# Microcontroller.net
KiCad netlist of a schematic drawn in Altium Designer
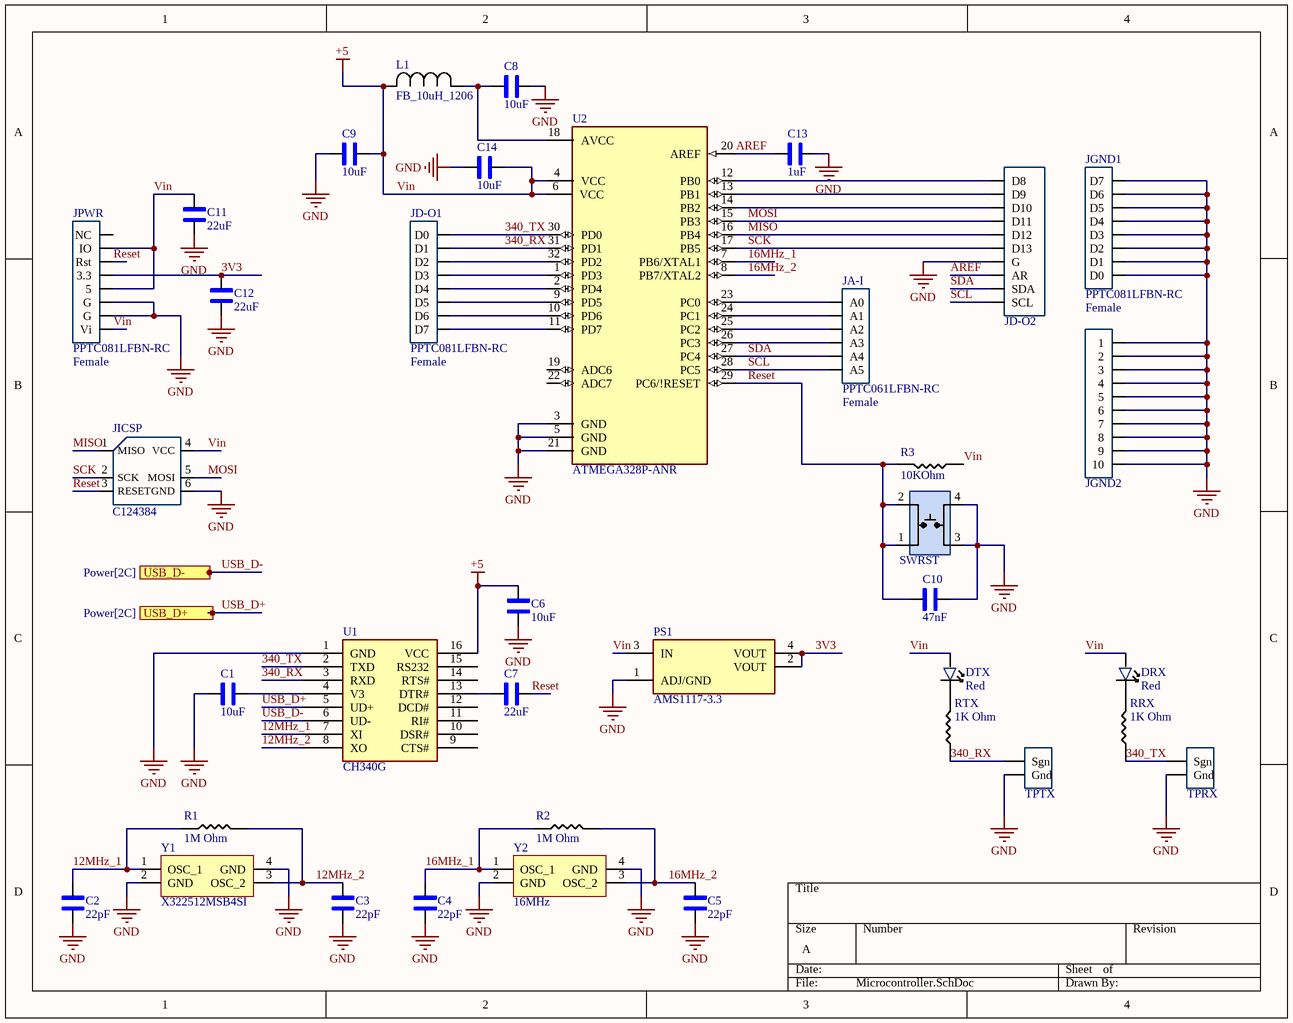
[diagram p0: Microcontroller.SchDoc]

(export (version "E")
  (design (tool "Eeschema 10.0.6"))
  (components
    (comp (ref "C1")
      (value "10uF")
      (footprint "1206_Passive_Capacitor")
      (description "10uF ±10% 50V X5R 1206 Multilayer Ceramic Capacitors MLCC - SMD/SMT RoHS")
      (fields (field (name "LCSC PART#") "C13585") (field (name "MFR PART #") "CL31A106KBHNNNE"))
      (libsource (lib "ECEN5730Lib") (part "C_10uF_1206"))
    )
    (comp (ref "C2")
      (value "22pF")
      (footprint "1206_Passive_Capacitor")
      (description "22pF ±5% 1kV C0G 1206 Multilayer Ceramic Capacitors MLCC - SMD/SMT RoHS")
      (fields (field (name "LCSC PART#") "C107174") (field (name "MFR PART #") "CC1206JKNPOCBN220"))
      (libsource (lib "ECEN5730Lib") (part "C_22pF_1206"))
    )
    (comp (ref "C3")
      (value "22pF")
      (footprint "1206_Passive_Capacitor")
      (description "22pF ±5% 1kV C0G 1206 Multilayer Ceramic Capacitors MLCC - SMD/SMT RoHS")
      (fields (field (name "LCSC PART#") "C107174") (field (name "MFR PART #") "CC1206JKNPOCBN220"))
      (libsource (lib "ECEN5730Lib") (part "C_22pF_1206"))
    )
    (comp (ref "C4")
      (value "22pF")
      (footprint "1206_Passive_Capacitor")
      (description "22pF ±5% 1kV C0G 1206 Multilayer Ceramic Capacitors MLCC - SMD/SMT RoHS")
      (fields (field (name "LCSC PART#") "C107174") (field (name "MFR PART #") "CC1206JKNPOCBN220"))
      (libsource (lib "ECEN5730Lib") (part "C_22pF_1206"))
    )
    (comp (ref "C5")
      (value "22pF")
      (footprint "1206_Passive_Capacitor")
      (description "22pF ±5% 1kV C0G 1206 Multilayer Ceramic Capacitors MLCC - SMD/SMT RoHS")
      (fields (field (name "LCSC PART#") "C107174") (field (name "MFR PART #") "CC1206JKNPOCBN220"))
      (libsource (lib "ECEN5730Lib") (part "C_22pF_1206"))
    )
    (comp (ref "C6")
      (value "10uF")
      (footprint "1206_Passive_Capacitor")
      (description "10uF ±10% 50V X5R 1206 Multilayer Ceramic Capacitors MLCC - SMD/SMT RoHS")
      (fields (field (name "LCSC PART#") "C13585") (field (name "MFR PART #") "CL31A106KBHNNNE"))
      (libsource (lib "ECEN5730Lib") (part "C_10uF_1206"))
    )
    (comp (ref "C7")
      (value "22uF")
      (footprint "1206_Passive_Capacitor")
      (description "22uF ±10% 25V X5R 1206 Multilayer Ceramic Capacitors MLCC - SMD/SMT RoHS")
      (fields (field (name "MFR PART #") "CL31A226KAHNNNE") (field (name "LCSC PART#") "C12891"))
      (libsource (lib "ECEN5730Lib") (part "C_22uF_1206"))
    )
    (comp (ref "C8")
      (value "10uF")
      (footprint "1206_Passive_Capacitor")
      (description "10uF ±10% 50V X5R 1206 Multilayer Ceramic Capacitors MLCC - SMD/SMT RoHS")
      (fields (field (name "LCSC PART#") "C13585") (field (name "MFR PART #") "CL31A106KBHNNNE"))
      (libsource (lib "ECEN5730Lib") (part "C_10uF_1206"))
    )
    (comp (ref "C9")
      (value "10uF")
      (footprint "1206_Passive_Capacitor")
      (description "10uF ±10% 50V X5R 1206 Multilayer Ceramic Capacitors MLCC - SMD/SMT RoHS")
      (fields (field (name "LCSC PART#") "C13585") (field (name "MFR PART #") "CL31A106KBHNNNE"))
      (libsource (lib "ECEN5730Lib") (part "C_10uF_1206"))
    )
    (comp (ref "C10")
      (value "47nF")
      (footprint "1206_Passive_Capacitor")
      (description "47nF ±5% 50V C0G 1206 Multilayer Ceramic Capacitors MLCC - SMD/SMT RoHS")
      (fields (field (name "LCSC PART#") "C21812") (field (name "MFR PART #") "GRM31M5C1H473JA01L"))
      (libsource (lib "ECEN5730Lib") (part "C_47nF_1206"))
    )
    (comp (ref "C11")
      (value "22uF")
      (footprint "1206_Passive_Capacitor")
      (description "22uF ±10% 25V X5R 1206 Multilayer Ceramic Capacitors MLCC - SMD/SMT RoHS")
      (fields (field (name "MFR PART #") "CL31A226KAHNNNE") (field (name "LCSC PART#") "C12891"))
      (libsource (lib "ECEN5730Lib") (part "C_22uF_1206"))
    )
    (comp (ref "C12")
      (value "22uF")
      (footprint "1206_Passive_Capacitor")
      (description "22uF ±10% 25V X5R 1206 Multilayer Ceramic Capacitors MLCC - SMD/SMT RoHS")
      (fields (field (name "MFR PART #") "CL31A226KAHNNNE") (field (name "LCSC PART#") "C12891"))
      (libsource (lib "ECEN5730Lib") (part "C_22uF_1206"))
    )
    (comp (ref "C13")
      (value "1uF")
      (footprint "1206_Passive_Capacitor")
      (description "MULTILAYER CERAMIC CAPACITORS MLCC - SMD/SMT 1UF 50V 1206 ROHS")
      (fields (field (name "MFR PART #") "CL31B105KBHNNNE") (field (name "LCSC PART#") "C1848"))
      (libsource (lib "ECEN5730Lib") (part "C_1uF_1206"))
    )
    (comp (ref "C14")
      (value "10uF")
      (footprint "1206_Passive_Capacitor")
      (description "10uF ±10% 50V X5R 1206 Multilayer Ceramic Capacitors MLCC - SMD/SMT RoHS")
      (fields (field (name "LCSC PART#") "C13585") (field (name "MFR PART #") "CL31A106KBHNNNE"))
      (libsource (lib "ECEN5730Lib") (part "C_10uF_1206"))
    )
    (comp (ref "DRX")
      (value "Red")
      (footprint "LED_1206")
      (description "Red 621~631nm 1206 Light Emitting Diodes (LED) RoHS")
      (fields (field (name "MFR PART #") "15-21/R6C-FQ1R1B/2T") (field (name "LCSC PART#") "C93133"))
      (libsource (lib "ECEN5730Lib") (part "LED_RED_1206"))
    )
    (comp (ref "DTX")
      (value "Red")
      (footprint "LED_1206")
      (description "Red 621~631nm 1206 Light Emitting Diodes (LED) RoHS")
      (fields (field (name "MFR PART #") "15-21/R6C-FQ1R1B/2T") (field (name "LCSC PART#") "C93133"))
      (libsource (lib "ECEN5730Lib") (part "LED_RED_1206"))
    )
    (comp (ref "JA-I")
      (value "PPTC061LFBN-RC")
      (footprint "6_PIN_ARD-Analog_100mil")
      (description "6 Position Header Connector 0.100\" (2.54mm) Through Hole Tin")
      (fields (field (name "LCSC PART#") "C40877") (field (name "ALTIUM_VALUE") "Female"))
      (libsource (lib "ECEN5730Lib") (part "JF_6_PIN_FEMA_ARD-Anolog"))
    )
    (comp (ref "JD-O1")
      (value "PPTC081LFBN-RC")
      (footprint "8_PIN_ARD-DIG_100MIL")
      (description "8 Position Header Connector 0.100\" (2.54mm) Through Hole Tin")
      (fields (field (name "LCSC PART#") "C27438") (field (name "ALTIUM_VALUE") "Female"))
      (libsource (lib "ECEN5730Lib") (part "JF_8_PIN_FEMA_ARD-Dig"))
    )
    (comp (ref "JD-O2")
      (value "PPTC101LFBN-RC")
      (footprint "10_PIN_ARDUINO_100MIL")
      (description "10 Position Header Connector 0.100\" (2.54mm) Through Hole Tin")
      (fields (field (name "LCSC PART#") "C225507"))
      (libsource (lib "ECEN5730Lib") (part "JF_10_PIN_FEMA_ARDUINO"))
    )
    (comp (ref "JGND1")
      (value "PPTC081LFBN-RC")
      (footprint "8_PIN_ARD-DIG_100MIL")
      (description "8 Position Header Connector 0.100\" (2.54mm) Through Hole Tin")
      (fields (field (name "LCSC PART#") "C27438") (field (name "ALTIUM_VALUE") "Female"))
      (libsource (lib "") (part "JF_8_PIN_FEMA_ARD-Dig_1"))
    )
    (comp (ref "JGND2")
      (value "PPTC101LFBN-RC")
      (footprint "10_PIN_100MIL - Female")
      (description "10 Position Header Connector 0.100\" (2.54mm) Through Hole Tin")
      (fields (field (name "LCSC PART#") "C225507"))
      (libsource (lib "ECEN5730Lib") (part "JF_10_PIN_FEMALE_"))
    )
    (comp (ref "JICSP")
      (value "NRPN032PAEN-RC")
      (footprint "ICSP")
      (description "Connector Header Through Hole 6 position 0.079\" (2.00mm)")
      (fields (field (name "LCSC PART#") "C124384"))
      (libsource (lib "ECEN5730Lib") (part "J_ICSP"))
    )
    (comp (ref "JPWR")
      (value "PPTC081LFBN-RC")
      (footprint "8_PIN_ARD-PWR_100MIL")
      (description "8 Position Header Connector 0.100\" (2.54mm) Through Hole Tin")
      (fields (field (name "LCSC PART#") "C27438") (field (name "ALTIUM_VALUE") "Female"))
      (libsource (lib "ECEN5730Lib") (part "JF_8_PIN_FEMA_ARD-Pwr"))
    )
    (comp (ref "L1")
      (value "FB_10uH_1206")
      (footprint "AIML-1206_ABR-M")
      (description "25mA 10uH ±10% 800mΩ 1206  Inductors (SMD) ROHS")
      (fields (field (name "MFR PART #") "CMI321609X100KT") (field (name "LCSC PART#") "C1051"))
      (libsource (lib "ECEN5730Lib") (part "FB_10uH_1206"))
    )
    (comp (ref "PS1")
      (value "AMS1117-3.3")
      (footprint "LDO")
      (description "LOW DROPOUT REGULATORS(LDO) POSITIVE FIXED 1.3V @ 800MA 15V 3.3V 1A SOT-223 ROHS")
      (fields (field (name "LCSC PART#") "C6186"))
      (libsource (lib "ECEN5730Lib") (part "PS_AMS_LDO_3v3"))
    )
    (comp (ref "R1")
      (value "1M Ohm")
      (footprint "1206_Passive_Resitor")
      (description "CHIP RESISTOR - SURFACE MOUNT 1MOHMS ±1% 1/4W 1206 ROHS")
      (fields (field (name "MFR PART #") "RMCF1206JT1M00") (field (name "LCSC PART#") "C17927"))
      (libsource (lib "ECEN5730Lib") (part "R_1M_1206"))
    )
    (comp (ref "R2")
      (value "1M Ohm")
      (footprint "1206_Passive_Resitor")
      (description "CHIP RESISTOR - SURFACE MOUNT 1MOHMS ±1% 1/4W 1206 ROHS")
      (fields (field (name "MFR PART #") "RMCF1206JT1M00") (field (name "LCSC PART#") "C17927"))
      (libsource (lib "ECEN5730Lib") (part "R_1M_1206"))
    )
    (comp (ref "R3")
      (value "10KOhm")
      (footprint "1206_Passive_Resitor")
      (description "10 kOhms ±5% 0.25W, 1/4W Chip Resistor 1206 (3216 Metric) Automotive AEC-Q200 Thick Film")
      (fields (field (name "MFR PART #") "RMCF1206FT10K0") (field (name "LCSC PART#") "C17902"))
      (libsource (lib "ECEN5730Lib") (part "R_10KOhm_1206"))
    )
    (comp (ref "RRX")
      (value "1K Ohm")
      (footprint "1206_Passive_Resitor")
      (description "CHIP RESISTOR - SURFACE MOUNT 1KOHMS ±1% 1/4W 1206 ROHS")
      (fields (field (name "MFR PART #") "RNCP1206FTD1K00CT") (field (name "LCSC PART#") "C4410"))
      (libsource (lib "ECEN5730Lib") (part "R_1K_1206"))
    )
    (comp (ref "RTX")
      (value "1K Ohm")
      (footprint "1206_Passive_Resitor")
      (description "CHIP RESISTOR - SURFACE MOUNT 1KOHMS ±1% 1/4W 1206 ROHS")
      (fields (field (name "MFR PART #") "RNCP1206FTD1K00CT") (field (name "LCSC PART#") "C4410"))
      (libsource (lib "ECEN5730Lib") (part "R_1K_1206"))
    )
    (comp (ref "SWRST")
      (value "TL3305AF160QG")
      (footprint "Switch_JLC")
      (description "Tactile Switch SPST-NO Top Actuated Surface Mount")
      (fields (field (name "MFR PART #") "KH-4.5X4.5X4.3H-STM") (field (name "LCSC PART#") "C2837550"))
      (libsource (lib "ECEN5730Lib") (part "SW_Push_Button_JLC"))
    )
    (comp (ref "TPRX")
      (value "10x Probe TP")
      (footprint "TP10x_Probe")
      (description "Test Point 300 mil centers")
      (libsource (lib "ECEN5730Lib") (part "TP_10x_Probe"))
    )
    (comp (ref "TPTX")
      (value "10x Probe TP")
      (footprint "TP10x_Probe")
      (description "Test Point 300 mil centers")
      (libsource (lib "ECEN5730Lib") (part "TP_10x_Probe"))
    )
    (comp (ref "U1")
      (value "CH340G")
      (footprint "USB to serial")
      (description "Transceiver USB 2.0 2Mbps SOP-16_150mil USB ICs RoHS")
      (fields (field (name "LCSC PART#") "C14267"))
      (libsource (lib "ECEN5730Lib") (part "U_USBtoSerial"))
    )
    (comp (ref "U2")
      (value "ATMEGA328P-ANR")
      (footprint "ATMega328P")
      (description "AVR AVR® ATmega Microcontroller IC 8-Bit 20MHz 32KB (16K x 16) FLASH 32-TQFP (7x7)")
      (fields (field (name "MFR PART #") "ATMEGA328P-AU") (field (name "LCSC PART#") "C14877"))
      (libsource (lib "ECEN5730Lib") (part "U_ATMega328P"))
    )
    (comp (ref "Y1")
      (value "X322512MSB4SI")
      (footprint "Crystal resonator")
      (description "SMD Crystal Resonators 12MHz ±10ppm SMD-3225_4P RoHS")
      (fields (field (name "LCSC PART#") "C9002"))
      (libsource (lib "ECEN5730Lib") (part "X_12MHz_Res"))
    )
    (comp (ref "Y2")
      (value "16MHz")
      (footprint "Crystal resonator")
      (description "±10ppm 16000000Hz -40℃~85℃ 贴片无源晶振 60Ω 9pF SMD3225-4P Crystals ROHS")
      (fields (field (name "LCSC PART#") "C13738") (field (name "MFR PART #") "X322516MLB4SI"))
      (libsource (lib "ECEN5730Lib") (part "X_16Mhz_Res"))
    )
  )
  (nets
    (net (code "1") (name "+5") (class "Default")
      (node (ref "C11") (pin "2") (pinfunction "2_2") (pintype "passive"))
      (node (ref "C14") (pin "1") (pinfunction "1_1") (pintype "passive"))
      (node (ref "C6") (pin "2") (pinfunction "2_2") (pintype "passive"))
      (node (ref "C9") (pin "1") (pinfunction "1_1") (pintype "passive"))
      (node (ref "DRX") (pin "1") (pinfunction "1_1") (pintype "passive"))
      (node (ref "DTX") (pin "1") (pinfunction "1_1") (pintype "passive"))
      (node (ref "JICSP") (pin "4") (pinfunction "VCC_4") (pintype "passive"))
      (node (ref "JPWR") (pin "2") (pinfunction "IO_2") (pintype "passive"))
      (node (ref "JPWR") (pin "5") (pinfunction "5_5") (pintype "passive"))
      (node (ref "JPWR") (pin "8") (pinfunction "Vi_8") (pintype "passive"))
      (node (ref "L1") (pin "2") (pinfunction "2_2") (pintype "passive"))
      (node (ref "PS1") (pin "3") (pinfunction "IN_3") (pintype "power_in"))
      (node (ref "R3") (pin "1") (pinfunction "1_1") (pintype "passive"))
      (node (ref "U1") (pin "16") (pinfunction "VCC_16") (pintype "passive"))
      (node (ref "U2") (pin "4") (pinfunction "VCC_4") (pintype "power_in"))
      (node (ref "U2") (pin "6") (pinfunction "VCC_6") (pintype "power_in"))
    )
    (net (code "2") (name "/3V3") (class "Default")
      (node (ref "C12") (pin "2") (pinfunction "2_2") (pintype "passive"))
      (node (ref "JPWR") (pin "4") (pinfunction "3.3_4") (pintype "passive"))
      (node (ref "PS1") (pin "2") (pinfunction "VOUT_2") (pintype "power_in"))
      (node (ref "PS1") (pin "4") (pinfunction "VOUT_4") (pintype "power_in"))
    )
    (net (code "3") (name "/12MHz_1") (class "Default")
      (node (ref "C2") (pin "2") (pinfunction "2_2") (pintype "passive"))
      (node (ref "R1") (pin "1") (pinfunction "1_1") (pintype "passive"))
      (node (ref "U1") (pin "7") (pinfunction "XI_7") (pintype "passive"))
      (node (ref "Y1") (pin "1") (pinfunction "OSC_1_1") (pintype "passive"))
    )
    (net (code "4") (name "/12MHz_2") (class "Default")
      (node (ref "C3") (pin "2") (pinfunction "2_2") (pintype "passive"))
      (node (ref "R1") (pin "2") (pinfunction "2_2") (pintype "passive"))
      (node (ref "U1") (pin "8") (pinfunction "XO_8") (pintype "passive"))
      (node (ref "Y1") (pin "3") (pinfunction "OSC_2_3") (pintype "passive"))
    )
    (net (code "5") (name "/16MHz_1") (class "Default")
      (node (ref "C4") (pin "2") (pinfunction "2_2") (pintype "passive"))
      (node (ref "R2") (pin "1") (pinfunction "1_1") (pintype "passive"))
      (node (ref "U2") (pin "7") (pinfunction "PB6/XTAL1_7") (pintype "bidirectional"))
      (node (ref "Y2") (pin "1") (pinfunction "OSC_1_1") (pintype "passive"))
    )
    (net (code "6") (name "/16MHz_2") (class "Default")
      (node (ref "C5") (pin "2") (pinfunction "2_2") (pintype "passive"))
      (node (ref "R2") (pin "2") (pinfunction "2_2") (pintype "passive"))
      (node (ref "U2") (pin "8") (pinfunction "PB7/XTAL2_8") (pintype "bidirectional"))
      (node (ref "Y2") (pin "3") (pinfunction "OSC_2_3") (pintype "passive"))
    )
    (net (code "7") (name "/340_RX") (class "Default")
      (node (ref "JD-O1") (pin "7") (pinfunction "D1_7") (pintype "passive"))
      (node (ref "RTX") (pin "1") (pinfunction "1_1") (pintype "passive"))
      (node (ref "TPTX") (pin "1") (pinfunction "Sgn_1") (pintype "passive"))
      (node (ref "U1") (pin "3") (pinfunction "RXD_3") (pintype "passive"))
      (node (ref "U2") (pin "31") (pinfunction "PD1_31") (pintype "bidirectional"))
    )
    (net (code "8") (name "/340_TX") (class "Default")
      (node (ref "JD-O1") (pin "8") (pinfunction "D0_8") (pintype "passive"))
      (node (ref "RRX") (pin "1") (pinfunction "1_1") (pintype "passive"))
      (node (ref "TPRX") (pin "1") (pinfunction "Sgn_1") (pintype "passive"))
      (node (ref "U1") (pin "2") (pinfunction "TXD_2") (pintype "passive"))
      (node (ref "U2") (pin "30") (pinfunction "PD0_30") (pintype "bidirectional"))
    )
    (net (code "9") (name "/AREF") (class "Default")
      (node (ref "C13") (pin "1") (pinfunction "1_1") (pintype "passive"))
      (node (ref "JD-O2") (pin "3") (pinfunction "AR_3") (pintype "passive"))
      (node (ref "U2") (pin "20") (pinfunction "AREF_20") (pintype "input"))
    )
    (net (code "10") (name "/MISO") (class "Default")
      (node (ref "JD-O2") (pin "6") (pinfunction "D12_6") (pintype "passive"))
      (node (ref "JICSP") (pin "1") (pinfunction "MISO_1") (pintype "passive"))
      (node (ref "U2") (pin "16") (pinfunction "PB4_16") (pintype "bidirectional"))
    )
    (net (code "11") (name "/MOSI") (class "Default")
      (node (ref "JD-O2") (pin "7") (pinfunction "D11_7") (pintype "passive"))
      (node (ref "JICSP") (pin "5") (pinfunction "MOSI_5") (pintype "passive"))
      (node (ref "U2") (pin "15") (pinfunction "PB3_15") (pintype "bidirectional"))
    )
    (net (code "12") (name "/Reset") (class "Default")
      (node (ref "C10") (pin "2") (pinfunction "2_2") (pintype "passive"))
      (node (ref "C7") (pin "2") (pinfunction "2_2") (pintype "passive"))
      (node (ref "JICSP") (pin "3") (pinfunction "RESET_3") (pintype "passive"))
      (node (ref "JPWR") (pin "3") (pinfunction "Rst_3") (pintype "passive"))
      (node (ref "R3") (pin "2") (pinfunction "2_2") (pintype "passive"))
      (node (ref "SWRST") (pin "1") (pinfunction "1_1") (pintype "passive"))
      (node (ref "SWRST") (pin "2") (pinfunction "2_2") (pintype "passive"))
      (node (ref "U2") (pin "29") (pinfunction "PC6/!RESET_29") (pintype "bidirectional"))
    )
    (net (code "13") (name "/SCK") (class "Default")
      (node (ref "JD-O2") (pin "5") (pinfunction "D13_5") (pintype "passive"))
      (node (ref "JICSP") (pin "2") (pinfunction "SCK_2") (pintype "passive"))
      (node (ref "U2") (pin "17") (pinfunction "PB5_17") (pintype "bidirectional"))
    )
    (net (code "14") (name "/SCL") (class "Default")
      (node (ref "JA-I") (pin "6") (pinfunction "A5_6") (pintype "passive"))
      (node (ref "JD-O2") (pin "1") (pinfunction "SCL_1") (pintype "passive"))
      (node (ref "U2") (pin "28") (pinfunction "PC5_28") (pintype "bidirectional"))
    )
    (net (code "15") (name "/SDA") (class "Default")
      (node (ref "JA-I") (pin "5") (pinfunction "A4_5") (pintype "passive"))
      (node (ref "JD-O2") (pin "2") (pinfunction "SDA_2") (pintype "passive"))
      (node (ref "U2") (pin "27") (pinfunction "PC4_27") (pintype "bidirectional"))
    )
    (net (code "16") (name "/USB_D+") (class "Default")
      (node (ref "U1") (pin "5") (pinfunction "UD+_5") (pintype "passive"))
    )
    (net (code "17") (name "/USB_D-") (class "Default")
      (node (ref "U1") (pin "6") (pinfunction "UD-_6") (pintype "passive"))
    )
    (net (code "18") (name "GND") (class "Default")
      (node (ref "C1") (pin "1") (pinfunction "1_1") (pintype "passive"))
      (node (ref "C10") (pin "1") (pinfunction "1_1") (pintype "passive"))
      (node (ref "C11") (pin "1") (pinfunction "1_1") (pintype "passive"))
      (node (ref "C12") (pin "1") (pinfunction "1_1") (pintype "passive"))
      (node (ref "C13") (pin "2") (pinfunction "2_2") (pintype "passive"))
      (node (ref "C14") (pin "2") (pinfunction "2_2") (pintype "passive"))
      (node (ref "C2") (pin "1") (pinfunction "1_1") (pintype "passive"))
      (node (ref "C3") (pin "1") (pinfunction "1_1") (pintype "passive"))
      (node (ref "C4") (pin "1") (pinfunction "1_1") (pintype "passive"))
      (node (ref "C5") (pin "1") (pinfunction "1_1") (pintype "passive"))
      (node (ref "C6") (pin "1") (pinfunction "1_1") (pintype "passive"))
      (node (ref "C8") (pin "1") (pinfunction "1_1") (pintype "passive"))
      (node (ref "C9") (pin "2") (pinfunction "2_2") (pintype "passive"))
      (node (ref "JD-O2") (pin "4") (pinfunction "G_4") (pintype "passive"))
      (node (ref "JGND1") (pin "1") (pinfunction "D7_1") (pintype "passive"))
      (node (ref "JGND1") (pin "2") (pinfunction "D6_2") (pintype "passive"))
      (node (ref "JGND1") (pin "3") (pinfunction "D5_3") (pintype "passive"))
      (node (ref "JGND1") (pin "4") (pinfunction "D4_4") (pintype "passive"))
      (node (ref "JGND1") (pin "5") (pinfunction "D3_5") (pintype "passive"))
      (node (ref "JGND1") (pin "6") (pinfunction "D2_6") (pintype "passive"))
      (node (ref "JGND1") (pin "7") (pinfunction "D1_7") (pintype "passive"))
      (node (ref "JGND1") (pin "8") (pinfunction "D0_8") (pintype "passive"))
      (node (ref "JGND2") (pin "1") (pinfunction "1_1") (pintype "passive"))
      (node (ref "JGND2") (pin "10") (pinfunction "10_10") (pintype "passive"))
      (node (ref "JGND2") (pin "2") (pinfunction "2_2") (pintype "passive"))
      (node (ref "JGND2") (pin "3") (pinfunction "3_3") (pintype "passive"))
      (node (ref "JGND2") (pin "4") (pinfunction "4_4") (pintype "passive"))
      (node (ref "JGND2") (pin "5") (pinfunction "5_5") (pintype "passive"))
      (node (ref "JGND2") (pin "6") (pinfunction "6_6") (pintype "passive"))
      (node (ref "JGND2") (pin "7") (pinfunction "7_7") (pintype "passive"))
      (node (ref "JGND2") (pin "8") (pinfunction "8_8") (pintype "passive"))
      (node (ref "JGND2") (pin "9") (pinfunction "9_9") (pintype "passive"))
      (node (ref "JICSP") (pin "6") (pinfunction "GND_6") (pintype "passive"))
      (node (ref "JPWR") (pin "6") (pinfunction "G_6") (pintype "passive"))
      (node (ref "JPWR") (pin "7") (pinfunction "G_7") (pintype "passive"))
      (node (ref "PS1") (pin "1") (pinfunction "ADJ/GND_1") (pintype "passive"))
      (node (ref "SWRST") (pin "3") (pinfunction "3_3") (pintype "passive"))
      (node (ref "SWRST") (pin "4") (pinfunction "4_4") (pintype "passive"))
      (node (ref "TPRX") (pin "2") (pinfunction "Gnd_2") (pintype "passive"))
      (node (ref "TPTX") (pin "2") (pinfunction "Gnd_2") (pintype "passive"))
      (node (ref "U1") (pin "1") (pinfunction "GND_1") (pintype "passive"))
      (node (ref "U2") (pin "21") (pinfunction "GND_21") (pintype "power_in"))
      (node (ref "U2") (pin "3") (pinfunction "GND_3") (pintype "power_in"))
      (node (ref "U2") (pin "5") (pinfunction "GND_5") (pintype "power_in"))
      (node (ref "Y1") (pin "2") (pinfunction "GND_2") (pintype "passive"))
      (node (ref "Y1") (pin "4") (pinfunction "GND_4") (pintype "passive"))
      (node (ref "Y2") (pin "2") (pinfunction "GND_2") (pintype "passive"))
      (node (ref "Y2") (pin "4") (pinfunction "GND_4") (pintype "passive"))
    )
    (net (code "19") (name "Net-(DRX-Pad2)") (class "Default")
      (node (ref "DRX") (pin "2") (pinfunction "2_2") (pintype "passive"))
      (node (ref "RRX") (pin "2") (pinfunction "2_2") (pintype "passive"))
    )
    (net (code "20") (name "Net-(DTX-Pad2)") (class "Default")
      (node (ref "DTX") (pin "2") (pinfunction "2_2") (pintype "passive"))
      (node (ref "RTX") (pin "2") (pinfunction "2_2") (pintype "passive"))
    )
    (net (code "21") (name "Net-(JA-I-A0)") (class "Default")
      (node (ref "JA-I") (pin "1") (pinfunction "A0_1") (pintype "passive"))
      (node (ref "U2") (pin "23") (pinfunction "PC0_23") (pintype "bidirectional"))
    )
    (net (code "22") (name "Net-(JA-I-A1)") (class "Default")
      (node (ref "JA-I") (pin "2") (pinfunction "A1_2") (pintype "passive"))
      (node (ref "U2") (pin "24") (pinfunction "PC1_24") (pintype "bidirectional"))
    )
    (net (code "23") (name "Net-(JA-I-A2)") (class "Default")
      (node (ref "JA-I") (pin "3") (pinfunction "A2_3") (pintype "passive"))
      (node (ref "U2") (pin "25") (pinfunction "PC2_25") (pintype "bidirectional"))
    )
    (net (code "24") (name "Net-(JA-I-A3)") (class "Default")
      (node (ref "JA-I") (pin "4") (pinfunction "A3_4") (pintype "passive"))
      (node (ref "U2") (pin "26") (pinfunction "PC3_26") (pintype "bidirectional"))
    )
    (net (code "25") (name "Net-(JD-O1-D2)") (class "Default")
      (node (ref "JD-O1") (pin "6") (pinfunction "D2_6") (pintype "passive"))
      (node (ref "U2") (pin "32") (pinfunction "PD2_32") (pintype "bidirectional"))
    )
    (net (code "26") (name "Net-(JD-O1-D3)") (class "Default")
      (node (ref "JD-O1") (pin "5") (pinfunction "D3_5") (pintype "passive"))
      (node (ref "U2") (pin "1") (pinfunction "PD3_1") (pintype "bidirectional"))
    )
    (net (code "27") (name "Net-(JD-O1-D4)") (class "Default")
      (node (ref "JD-O1") (pin "4") (pinfunction "D4_4") (pintype "passive"))
      (node (ref "U2") (pin "2") (pinfunction "PD4_2") (pintype "bidirectional"))
    )
    (net (code "28") (name "Net-(JD-O1-D5)") (class "Default")
      (node (ref "JD-O1") (pin "3") (pinfunction "D5_3") (pintype "passive"))
      (node (ref "U2") (pin "9") (pinfunction "PD5_9") (pintype "bidirectional"))
    )
    (net (code "29") (name "Net-(JD-O1-D6)") (class "Default")
      (node (ref "JD-O1") (pin "2") (pinfunction "D6_2") (pintype "passive"))
      (node (ref "U2") (pin "10") (pinfunction "PD6_10") (pintype "bidirectional"))
    )
    (net (code "30") (name "Net-(JD-O1-D7)") (class "Default")
      (node (ref "JD-O1") (pin "1") (pinfunction "D7_1") (pintype "passive"))
      (node (ref "U2") (pin "11") (pinfunction "PD7_11") (pintype "bidirectional"))
    )
    (net (code "31") (name "Net-(JD-O2-D8)") (class "Default")
      (node (ref "JD-O2") (pin "10") (pinfunction "D8_10") (pintype "passive"))
      (node (ref "U2") (pin "12") (pinfunction "PB0_12") (pintype "bidirectional"))
    )
    (net (code "32") (name "Net-(JD-O2-D9)") (class "Default")
      (node (ref "JD-O2") (pin "9") (pinfunction "D9_9") (pintype "passive"))
      (node (ref "U2") (pin "13") (pinfunction "PB1_13") (pintype "bidirectional"))
    )
    (net (code "33") (name "Net-(JD-O2-D10)") (class "Default")
      (node (ref "JD-O2") (pin "8") (pinfunction "D10_8") (pintype "passive"))
      (node (ref "U2") (pin "14") (pinfunction "PB2_14") (pintype "bidirectional"))
    )
    (net (code "34") (name "Net-(U1-DTR#)") (class "Default")
      (node (ref "C7") (pin "1") (pinfunction "1_1") (pintype "passive"))
      (node (ref "U1") (pin "13") (pinfunction "DTR#_13") (pintype "passive"))
    )
    (net (code "35") (name "Net-(U1-V3)") (class "Default")
      (node (ref "C1") (pin "2") (pinfunction "2_2") (pintype "passive"))
      (node (ref "U1") (pin "4") (pinfunction "V3_4") (pintype "passive"))
    )
    (net (code "36") (name "Net-(U2-AVCC)") (class "Default")
      (node (ref "C8") (pin "2") (pinfunction "2_2") (pintype "passive"))
      (node (ref "L1") (pin "1") (pinfunction "1_1") (pintype "passive"))
      (node (ref "U2") (pin "18") (pinfunction "AVCC_18") (pintype "power_in"))
    )
    (net (code "37") (name "unconnected-(JPWR-NC-Pad1)") (class "Default")
      (node (ref "JPWR") (pin "1") (pinfunction "NC_1") (pintype "passive"))
    )
    (net (code "38") (name "unconnected-(U1-CTS#-Pad9)") (class "Default")
      (node (ref "U1") (pin "9") (pinfunction "CTS#_9") (pintype "passive"))
    )
    (net (code "39") (name "unconnected-(U1-DCD#-Pad12)") (class "Default")
      (node (ref "U1") (pin "12") (pinfunction "DCD#_12") (pintype "passive"))
    )
    (net (code "40") (name "unconnected-(U1-DSR#-Pad10)") (class "Default")
      (node (ref "U1") (pin "10") (pinfunction "DSR#_10") (pintype "passive"))
    )
    (net (code "41") (name "unconnected-(U1-RI#-Pad11)") (class "Default")
      (node (ref "U1") (pin "11") (pinfunction "RI#_11") (pintype "passive"))
    )
    (net (code "42") (name "unconnected-(U1-RS232-Pad15)") (class "Default")
      (node (ref "U1") (pin "15") (pinfunction "RS232_15") (pintype "passive"))
    )
    (net (code "43") (name "unconnected-(U1-RTS#-Pad14)") (class "Default")
      (node (ref "U1") (pin "14") (pinfunction "RTS#_14") (pintype "passive"))
    )
    (net (code "44") (name "unconnected-(U2-ADC6-Pad19)") (class "Default")
      (node (ref "U2") (pin "19") (pinfunction "ADC6_19") (pintype "bidirectional"))
    )
    (net (code "45") (name "unconnected-(U2-ADC7-Pad22)") (class "Default")
      (node (ref "U2") (pin "22") (pinfunction "ADC7_22") (pintype "bidirectional"))
    )
  )
)
